# STorM32_NT_logger_micro_v22g4_000.net
KiCad netlist of a schematic drawn in EAGLE
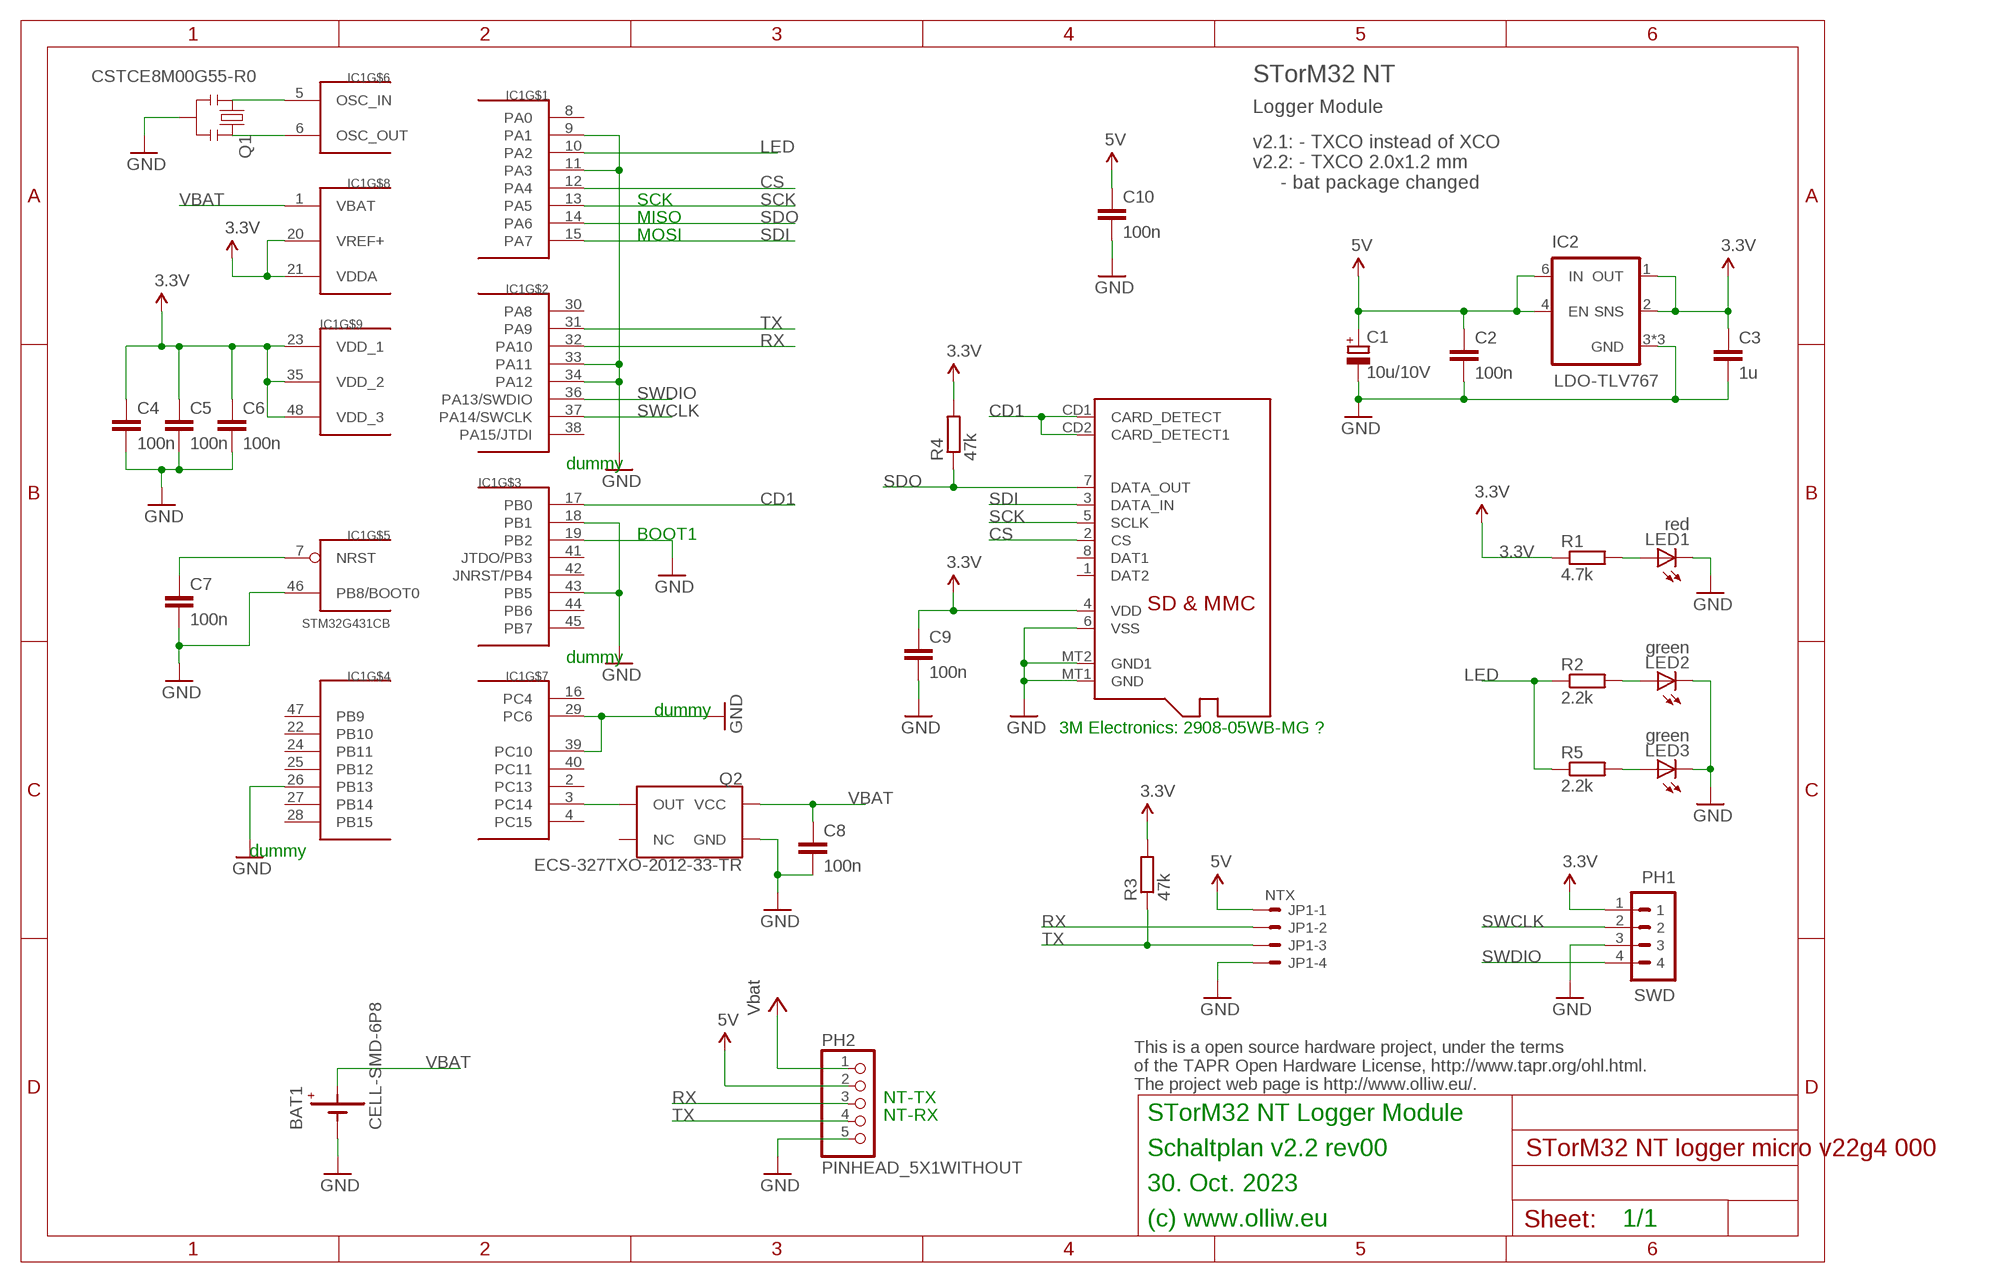
[diagram p0: schematic, sheet 1]

(export (version "E")
  (design (tool "Eeschema 10.0.6"))
  (components
    (comp (ref "BAT1")
      (value "CELL-SMD-6P8")
      (footprint "eagle-import:CELL-RECHARGABLE-6P8")
      (libsource (lib "eagle-import") (part "CELL-SMD-6P8"))
    )
    (comp (ref "C1")
      (value "10u/10V")
      (footprint "eagle-import:SMC_B")
      (libsource (lib "eagle-import") (part "CPOL-EUSMCB"))
    )
    (comp (ref "C2")
      (value "100n")
      (footprint "eagle-import:C0603")
      (libsource (lib "eagle-import") (part "C-EUC0603"))
    )
    (comp (ref "C3")
      (value "1u")
      (footprint "eagle-import:C0603")
      (libsource (lib "eagle-import") (part "C-EUC0603"))
    )
    (comp (ref "C4")
      (value "100n")
      (footprint "eagle-import:C0402")
      (libsource (lib "eagle-import") (part "C-EUC0402"))
    )
    (comp (ref "C5")
      (value "100n")
      (footprint "eagle-import:C0402")
      (libsource (lib "eagle-import") (part "C-EUC0402"))
    )
    (comp (ref "C6")
      (value "100n")
      (footprint "eagle-import:C0402")
      (libsource (lib "eagle-import") (part "C-EUC0402"))
    )
    (comp (ref "C7")
      (value "100n")
      (footprint "eagle-import:C0402")
      (libsource (lib "eagle-import") (part "C-EUC0402"))
    )
    (comp (ref "C8")
      (value "100n")
      (footprint "eagle-import:C0402")
      (libsource (lib "eagle-import") (part "C-EUC0402"))
    )
    (comp (ref "C9")
      (value "100n")
      (footprint "eagle-import:C0402")
      (libsource (lib "eagle-import") (part "C-EUC0402"))
    )
    (comp (ref "C10")
      (value "100n")
      (footprint "eagle-import:C0603")
      (libsource (lib "eagle-import") (part "C-EUC0603"))
    )
    (comp (ref "IC1")
      (value "STM32G431CB")
      (footprint "eagle-import:UFQFPN48")
      (libsource (lib "eagle-import") (part "STM32G4X1CX"))
    )
    (comp (ref "IC2")
      (value "LDO-TLV767")
      (footprint "eagle-import:WSON-6-2X2")
      (libsource (lib "eagle-import") (part "LDO-TLV767"))
    )
    (comp (ref "JP1")
      (value "NTX")
      (footprint "eagle-import:SM04B-SRSS-TB")
      (libsource (lib "eagle-import") (part "?M04B-SRSS-TBS"))
    )
    (comp (ref "LED1")
      (value "red")
      (footprint "eagle-import:CHIPLED_0603")
      (libsource (lib "eagle-import") (part "LEDCHIPLED_0603"))
    )
    (comp (ref "LED2")
      (value "green")
      (footprint "eagle-import:CHIPLED_0603")
      (libsource (lib "eagle-import") (part "LEDCHIPLED_0603"))
    )
    (comp (ref "LED3")
      (value "green")
      (footprint "eagle-import:CHIPLED_0603")
      (libsource (lib "eagle-import") (part "LEDCHIPLED_0603"))
    )
    (comp (ref "PH1")
      (value "SWD")
      (footprint "eagle-import:4X1_1P27_OCT_BILEX")
      (libsource (lib "eagle-import") (part "P4X1_1P27-OCT_BILEX"))
    )
    (comp (ref "PH2")
      (value "PINHEAD_5X1WITHOUT")
      (footprint "eagle-import:PINHEAD_5X1_WO")
      (libsource (lib "eagle-import") (part "PINHEAD_5X1WITHOUT"))
    )
    (comp (ref "Q1")
      (value "CSTCE8M00G55-R0")
      (footprint "eagle-import:RESONATOR-SMD")
      (libsource (lib "eagle-import") (part "RESONATORSMD"))
    )
    (comp (ref "Q2")
      (value "ECS-327TXO-2012-33-TR")
      (footprint "eagle-import:TXCO-20X12")
      (libsource (lib "eagle-import") (part "TXCO-2.0X1.2MM"))
    )
    (comp (ref "R1")
      (value "4.7k")
      (footprint "eagle-import:R0402")
      (libsource (lib "eagle-import") (part "R-EU_R0402"))
    )
    (comp (ref "R2")
      (value "2.2k")
      (footprint "eagle-import:R0402")
      (libsource (lib "eagle-import") (part "R-EU_R0402"))
    )
    (comp (ref "R3")
      (value "47k")
      (footprint "eagle-import:R0402")
      (libsource (lib "eagle-import") (part "R-EU_R0402"))
    )
    (comp (ref "R4")
      (value "47k")
      (footprint "eagle-import:R0402")
      (libsource (lib "eagle-import") (part "R-EU_R0402"))
    )
    (comp (ref "R5")
      (value "2.2k")
      (footprint "eagle-import:R0402")
      (libsource (lib "eagle-import") (part "R-EU_R0402"))
    )
    (comp (ref "U1")
      (value "3M 2908-05WB-MG ??")
      (footprint "eagle-import:MICROSD")
      (libsource (lib "eagle-import") (part "MICROSD"))
    )
  )
  (nets
    (net (code "1") (name "/CD1") (class "Default")
      (node (ref "IC1") (pin "17") (pinfunction "PB0_17") (pintype "bidirectional"))
      (node (ref "U1") (pin "CD1") (pinfunction "CARD_DETECT_CD1") (pintype "passive"))
      (node (ref "U1") (pin "CD2") (pinfunction "CARD_DETECT1_CD2") (pintype "passive"))
    )
    (net (code "2") (name "/CS") (class "Default")
      (node (ref "IC1") (pin "12") (pinfunction "PA4_12") (pintype "bidirectional"))
      (node (ref "U1") (pin "2") (pinfunction "CS_2") (pintype "input"))
    )
    (net (code "3") (name "/LED") (class "Default")
      (node (ref "IC1") (pin "10") (pinfunction "PA2_10") (pintype "bidirectional"))
      (node (ref "R2") (pin "1") (pinfunction "1_1") (pintype "passive"))
      (node (ref "R5") (pin "1") (pinfunction "1_1") (pintype "passive"))
    )
    (net (code "4") (name "/RX") (class "Default")
      (node (ref "IC1") (pin "32") (pinfunction "PA10_32") (pintype "bidirectional"))
      (node (ref "JP1") (pin "2") (pinfunction "S_2") (pintype "passive"))
      (node (ref "PH2") (pin "3") (pinfunction "3_3") (pintype "passive"))
    )
    (net (code "5") (name "/SCK") (class "Default")
      (node (ref "IC1") (pin "13") (pinfunction "PA5_13") (pintype "bidirectional"))
      (node (ref "U1") (pin "5") (pinfunction "SCLK_5") (pintype "input"))
    )
    (net (code "6") (name "/SDI") (class "Default")
      (node (ref "IC1") (pin "15") (pinfunction "PA7_15") (pintype "bidirectional"))
      (node (ref "U1") (pin "3") (pinfunction "DATA_IN_3") (pintype "input"))
    )
    (net (code "7") (name "/SDO") (class "Default")
      (node (ref "IC1") (pin "14") (pinfunction "PA6_14") (pintype "bidirectional"))
      (node (ref "R4") (pin "1") (pinfunction "1_1") (pintype "passive"))
      (node (ref "U1") (pin "7") (pinfunction "DATA_OUT_7") (pintype "output"))
    )
    (net (code "8") (name "/SWCLK") (class "Default")
      (node (ref "IC1") (pin "37") (pinfunction "PA14/SWCLK_37") (pintype "bidirectional"))
      (node (ref "PH1") (pin "2") (pinfunction "2_2") (pintype "passive"))
    )
    (net (code "9") (name "/SWDIO") (class "Default")
      (node (ref "IC1") (pin "36") (pinfunction "PA13/SWDIO_36") (pintype "bidirectional"))
      (node (ref "PH1") (pin "4") (pinfunction "4_4") (pintype "passive"))
    )
    (net (code "10") (name "/TX") (class "Default")
      (node (ref "IC1") (pin "31") (pinfunction "PA9_31") (pintype "bidirectional"))
      (node (ref "JP1") (pin "3") (pinfunction "S_3") (pintype "passive"))
      (node (ref "PH2") (pin "4") (pinfunction "4_4") (pintype "passive"))
      (node (ref "R3") (pin "1") (pinfunction "1_1") (pintype "passive"))
    )
    (net (code "11") (name "/VBAT") (class "Default")
      (node (ref "BAT1") (pin "P+") (pinfunction "BAT+_P+") (pintype "power_in"))
      (node (ref "C8") (pin "1") (pinfunction "1_1") (pintype "passive"))
      (node (ref "IC1") (pin "1") (pinfunction "VBAT_1") (pintype "power_in"))
      (node (ref "Q2") (pin "4") (pinfunction "VCC_4") (pintype "bidirectional"))
    )
    (net (code "12") (name "3.3V") (class "Default")
      (node (ref "C3") (pin "1") (pinfunction "1_1") (pintype "passive"))
      (node (ref "C4") (pin "1") (pinfunction "1_1") (pintype "passive"))
      (node (ref "C5") (pin "1") (pinfunction "1_1") (pintype "passive"))
      (node (ref "C6") (pin "1") (pinfunction "1_1") (pintype "passive"))
      (node (ref "C9") (pin "1") (pinfunction "1_1") (pintype "passive"))
      (node (ref "IC1") (pin "20") (pinfunction "VREF+_20") (pintype "input"))
      (node (ref "IC1") (pin "21") (pinfunction "VDDA_21") (pintype "power_in"))
      (node (ref "IC1") (pin "23") (pinfunction "VDD_1_23") (pintype "power_in"))
      (node (ref "IC1") (pin "35") (pinfunction "VDD_2_35") (pintype "power_in"))
      (node (ref "IC1") (pin "48") (pinfunction "VDD_3_48") (pintype "power_in"))
      (node (ref "IC2") (pin "1") (pinfunction "OUT_1") (pintype "output"))
      (node (ref "IC2") (pin "2") (pinfunction "SNS_2") (pintype "input"))
      (node (ref "PH1") (pin "1") (pinfunction "1_1") (pintype "passive"))
      (node (ref "R1") (pin "1") (pinfunction "1_1") (pintype "passive"))
      (node (ref "R3") (pin "2") (pinfunction "2_2") (pintype "passive"))
      (node (ref "R4") (pin "2") (pinfunction "2_2") (pintype "passive"))
      (node (ref "U1") (pin "4") (pinfunction "VDD_4") (pintype "power_in"))
    )
    (net (code "13") (name "5V") (class "Default")
      (node (ref "C1") (pin "+") (pinfunction "+_+") (pintype "passive"))
      (node (ref "C10") (pin "1") (pinfunction "1_1") (pintype "passive"))
      (node (ref "C2") (pin "1") (pinfunction "1_1") (pintype "passive"))
      (node (ref "IC2") (pin "4") (pinfunction "EN_4") (pintype "input"))
      (node (ref "IC2") (pin "6") (pinfunction "IN_6") (pintype "power_in"))
      (node (ref "JP1") (pin "1") (pinfunction "S_1") (pintype "passive"))
      (node (ref "PH2") (pin "2") (pinfunction "2_2") (pintype "passive"))
    )
    (net (code "14") (name "GND") (class "Default")
      (node (ref "BAT1") (pin "P-") (pinfunction "GND_P-") (pintype "power_in"))
      (node (ref "C1") (pin "-") (pinfunction "-_-") (pintype "passive"))
      (node (ref "C10") (pin "2") (pinfunction "2_2") (pintype "passive"))
      (node (ref "C2") (pin "2") (pinfunction "2_2") (pintype "passive"))
      (node (ref "C3") (pin "2") (pinfunction "2_2") (pintype "passive"))
      (node (ref "C4") (pin "2") (pinfunction "2_2") (pintype "passive"))
      (node (ref "C5") (pin "2") (pinfunction "2_2") (pintype "passive"))
      (node (ref "C6") (pin "2") (pinfunction "2_2") (pintype "passive"))
      (node (ref "C7") (pin "2") (pinfunction "2_2") (pintype "passive"))
      (node (ref "C8") (pin "2") (pinfunction "2_2") (pintype "passive"))
      (node (ref "C9") (pin "2") (pinfunction "2_2") (pintype "passive"))
      (node (ref "IC1") (pin "11") (pinfunction "PA3_11") (pintype "bidirectional"))
      (node (ref "IC1") (pin "18") (pinfunction "PB1_18") (pintype "bidirectional"))
      (node (ref "IC1") (pin "19") (pinfunction "PB2_19") (pintype "bidirectional"))
      (node (ref "IC1") (pin "26") (pinfunction "PB13_26") (pintype "bidirectional"))
      (node (ref "IC1") (pin "29") (pinfunction "PC6_29") (pintype "bidirectional"))
      (node (ref "IC1") (pin "33") (pinfunction "PA11_33") (pintype "bidirectional"))
      (node (ref "IC1") (pin "34") (pinfunction "PA12_34") (pintype "bidirectional"))
      (node (ref "IC1") (pin "39") (pinfunction "PC10_39") (pintype "bidirectional"))
      (node (ref "IC1") (pin "43") (pinfunction "PB5_43") (pintype "bidirectional"))
      (node (ref "IC1") (pin "46") (pinfunction "PB8/BOOT0_46") (pintype "input"))
      (node (ref "IC1") (pin "9") (pinfunction "PA1_9") (pintype "bidirectional"))
      (node (ref "IC2") (pin "3") (pinfunction "GND_3") (pintype "power_in"))
      (node (ref "IC2") (pin "5") (pinfunction "GND_5") (pintype "power_in"))
      (node (ref "IC2") (pin "7") (pinfunction "GND_7") (pintype "power_in"))
      (node (ref "JP1") (pin "4") (pinfunction "S_4") (pintype "passive"))
      (node (ref "LED1") (pin "C") (pinfunction "C_C") (pintype "passive"))
      (node (ref "LED2") (pin "C") (pinfunction "C_C") (pintype "passive"))
      (node (ref "LED3") (pin "C") (pinfunction "C_C") (pintype "passive"))
      (node (ref "PH1") (pin "3") (pinfunction "3_3") (pintype "passive"))
      (node (ref "PH2") (pin "5") (pinfunction "5_5") (pintype "passive"))
      (node (ref "Q1") (pin "2") (pinfunction "2_2") (pintype "passive"))
      (node (ref "Q2") (pin "2") (pinfunction "GND_2") (pintype "bidirectional"))
      (node (ref "U1") (pin "6") (pinfunction "VSS_6") (pintype "power_in"))
      (node (ref "U1") (pin "MT1") (pinfunction "GND_MT1") (pintype "power_in"))
      (node (ref "U1") (pin "MT2") (pinfunction "GND1_MT2") (pintype "power_in"))
    )
    (net (code "15") (name "Net-(IC1E-NRST)") (class "Default")
      (node (ref "C7") (pin "1") (pinfunction "1_1") (pintype "passive"))
      (node (ref "IC1") (pin "7") (pinfunction "NRST_7") (pintype "input"))
    )
    (net (code "16") (name "Net-(IC1F-OSC_IN)") (class "Default")
      (node (ref "IC1") (pin "5") (pinfunction "OSC_IN_5") (pintype "input"))
      (node (ref "Q1") (pin "1") (pinfunction "1_1") (pintype "passive"))
    )
    (net (code "17") (name "Net-(IC1F-OSC_OUT)") (class "Default")
      (node (ref "IC1") (pin "6") (pinfunction "OSC_OUT_6") (pintype "output"))
      (node (ref "Q1") (pin "3") (pinfunction "3_3") (pintype "passive"))
    )
    (net (code "18") (name "Net-(IC1G-PC14)") (class "Default")
      (node (ref "IC1") (pin "3") (pinfunction "PC14_3") (pintype "bidirectional"))
      (node (ref "Q2") (pin "3") (pinfunction "OUT_3") (pintype "bidirectional"))
    )
    (net (code "19") (name "Net-(LED1-PadA)") (class "Default")
      (node (ref "LED1") (pin "A") (pinfunction "A_A") (pintype "passive"))
      (node (ref "R1") (pin "2") (pinfunction "2_2") (pintype "passive"))
    )
    (net (code "20") (name "Net-(LED2-PadA)") (class "Default")
      (node (ref "LED2") (pin "A") (pinfunction "A_A") (pintype "passive"))
      (node (ref "R2") (pin "2") (pinfunction "2_2") (pintype "passive"))
    )
    (net (code "21") (name "Net-(LED3-PadA)") (class "Default")
      (node (ref "LED3") (pin "A") (pinfunction "A_A") (pintype "passive"))
      (node (ref "R5") (pin "2") (pinfunction "2_2") (pintype "passive"))
    )
    (net (code "22") (name "Vbat") (class "Default")
      (node (ref "PH2") (pin "1") (pinfunction "1_1") (pintype "passive"))
    )
    (net (code "23") (name "unconnected-(IC1A-PA0-Pad8)") (class "Default")
      (node (ref "IC1") (pin "8") (pinfunction "PA0_8") (pintype "bidirectional"))
    )
    (net (code "24") (name "unconnected-(IC1B-PA8-Pad30)") (class "Default")
      (node (ref "IC1") (pin "30") (pinfunction "PA8_30") (pintype "bidirectional"))
    )
    (net (code "25") (name "unconnected-(IC1B-PA15{slash}JTDI-Pad38)") (class "Default")
      (node (ref "IC1") (pin "38") (pinfunction "PA15/JTDI_38") (pintype "bidirectional"))
    )
    (net (code "26") (name "unconnected-(IC1C-JNRST{slash}PB4-Pad42)") (class "Default")
      (node (ref "IC1") (pin "42") (pinfunction "JNRST/PB4_42") (pintype "bidirectional"))
    )
    (net (code "27") (name "unconnected-(IC1C-JTDO{slash}PB3-Pad41)") (class "Default")
      (node (ref "IC1") (pin "41") (pinfunction "JTDO/PB3_41") (pintype "bidirectional"))
    )
    (net (code "28") (name "unconnected-(IC1C-PB6-Pad44)") (class "Default")
      (node (ref "IC1") (pin "44") (pinfunction "PB6_44") (pintype "bidirectional"))
    )
    (net (code "29") (name "unconnected-(IC1C-PB7-Pad45)") (class "Default")
      (node (ref "IC1") (pin "45") (pinfunction "PB7_45") (pintype "bidirectional"))
    )
    (net (code "30") (name "unconnected-(IC1D-PB9-Pad47)") (class "Default")
      (node (ref "IC1") (pin "47") (pinfunction "PB9_47") (pintype "bidirectional"))
    )
    (net (code "31") (name "unconnected-(IC1D-PB10-Pad22)") (class "Default")
      (node (ref "IC1") (pin "22") (pinfunction "PB10_22") (pintype "bidirectional"))
    )
    (net (code "32") (name "unconnected-(IC1D-PB11-Pad24)") (class "Default")
      (node (ref "IC1") (pin "24") (pinfunction "PB11_24") (pintype "bidirectional"))
    )
    (net (code "33") (name "unconnected-(IC1D-PB12-Pad25)") (class "Default")
      (node (ref "IC1") (pin "25") (pinfunction "PB12_25") (pintype "bidirectional"))
    )
    (net (code "34") (name "unconnected-(IC1D-PB14-Pad27)") (class "Default")
      (node (ref "IC1") (pin "27") (pinfunction "PB14_27") (pintype "bidirectional"))
    )
    (net (code "35") (name "unconnected-(IC1D-PB15-Pad28)") (class "Default")
      (node (ref "IC1") (pin "28") (pinfunction "PB15_28") (pintype "bidirectional"))
    )
    (net (code "36") (name "unconnected-(IC1G-PC4-Pad16)") (class "Default")
      (node (ref "IC1") (pin "16") (pinfunction "PC4_16") (pintype "bidirectional"))
    )
    (net (code "37") (name "unconnected-(IC1G-PC11-Pad40)") (class "Default")
      (node (ref "IC1") (pin "40") (pinfunction "PC11_40") (pintype "bidirectional"))
    )
    (net (code "38") (name "unconnected-(IC1G-PC13-Pad2)") (class "Default")
      (node (ref "IC1") (pin "2") (pinfunction "PC13_2") (pintype "bidirectional"))
    )
    (net (code "39") (name "unconnected-(IC1G-PC15-Pad4)") (class "Default")
      (node (ref "IC1") (pin "4") (pinfunction "PC15_4") (pintype "bidirectional"))
    )
    (net (code "40") (name "unconnected-(Q2-NC-Pad1)") (class "Default")
      (node (ref "Q2") (pin "1") (pinfunction "NC_1") (pintype "bidirectional"))
    )
    (net (code "41") (name "unconnected-(U1-DAT1-Pad8)") (class "Default")
      (node (ref "U1") (pin "8") (pinfunction "DAT1_8") (pintype "bidirectional"))
    )
    (net (code "42") (name "unconnected-(U1-DAT2-Pad1)") (class "Default")
      (node (ref "U1") (pin "1") (pinfunction "DAT2_1") (pintype "bidirectional"))
    )
  )
)
